# TelematicsBoard.net
KiCad netlist of a schematic drawn in EAGLE
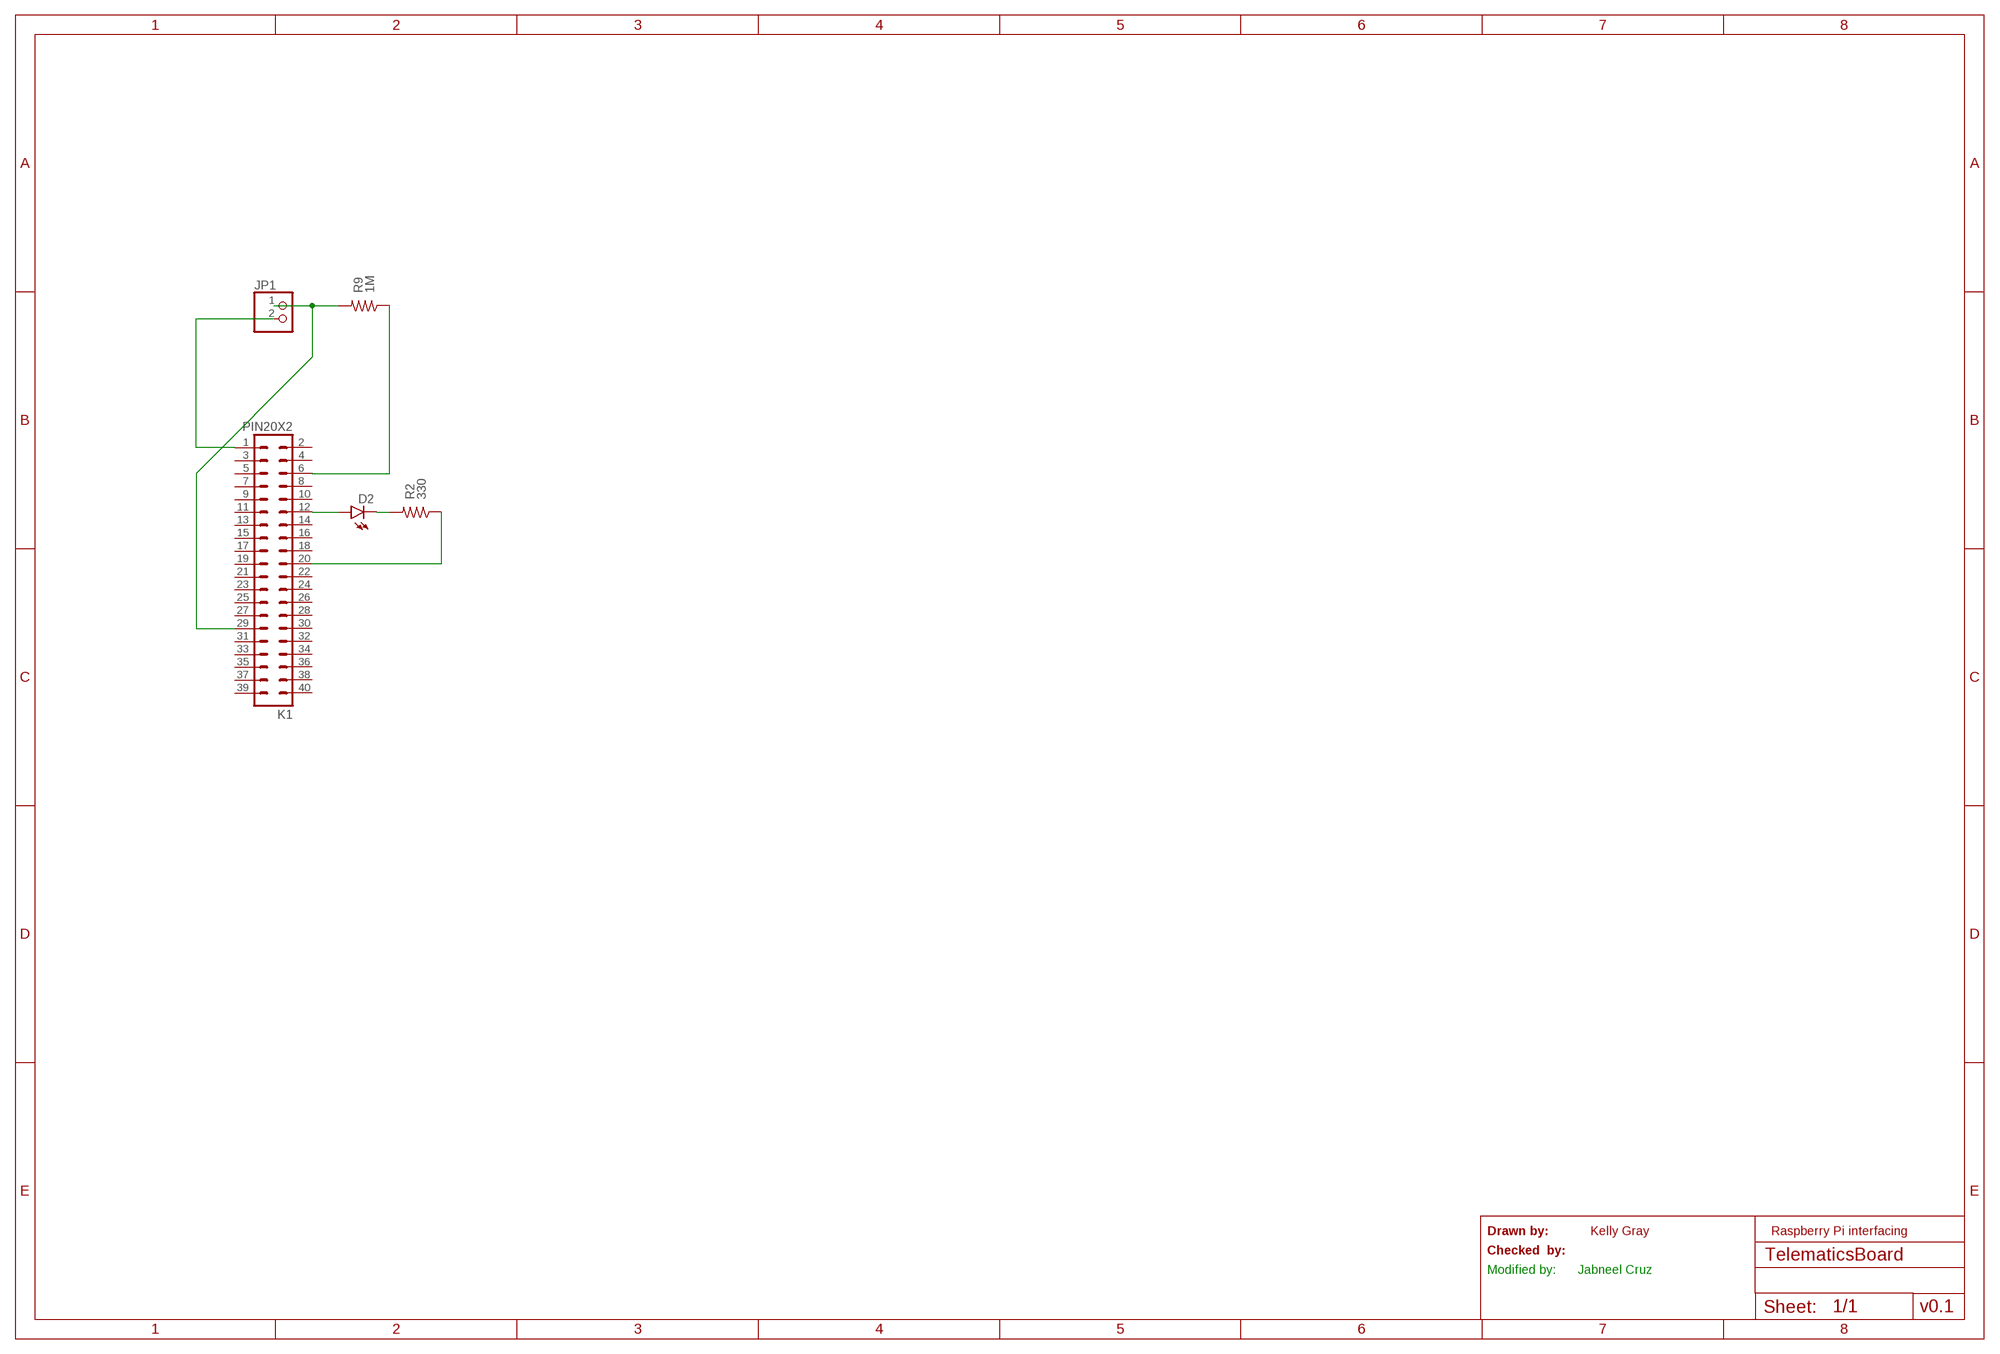
[diagram p0: schematic, sheet 1]

(export (version "E")
  (design (tool "Eeschema 10.0.6"))
  (components
    (comp (ref "D2")
      (value "LED-3MM-NO_SILK")
      (footprint "eagle-import:LED3MM-NS")
      (libsource (lib "eagle-import") (part "LED-3MM-NO_SILK"))
    )
    (comp (ref "JP1")
      (value "PINHD-1X2")
      (footprint "eagle-import:1X02")
      (libsource (lib "eagle-import") (part "PINHD-1X2"))
    )
    (comp (ref "K1")
      (value "PIN20X2")
      (footprint "eagle-import:PIN_20X2")
      (libsource (lib "eagle-import") (part "PIN20X2"))
    )
    (comp (ref "R2")
      (value "330")
      (footprint "eagle-import:AXIAL-0.3")
      (fields (field (name "TOLERANCE") "5%"))
      (libsource (lib "eagle-import") (part "1KOHM-1/4W-1%(PTH)"))
    )
    (comp (ref "R9")
      (value "1M")
      (footprint "eagle-import:AXIAL-0.3")
      (fields (field (name "TOLERANCE") "5%"))
      (libsource (lib "eagle-import") (part "1KOHM-1/4W-1%(PTH)"))
    )
  )
  (nets
    (net (code "1") (name "Net-(D2-C)") (class "Default")
      (node (ref "D2") (pin "K") (pinfunction "C_K") (pintype "passive"))
      (node (ref "R2") (pin "P$2") (pinfunction "2_P$2") (pintype "passive"))
    )
    (net (code "2") (name "Net-(D2-PadA)") (class "Default")
      (node (ref "D2") (pin "A") (pinfunction "A_A") (pintype "passive"))
      (node (ref "K1") (pin "12") (pinfunction "12_12") (pintype "passive"))
    )
    (net (code "3") (name "Net-(JP1-Pad2)") (class "Default")
      (node (ref "JP1") (pin "2") (pinfunction "2_2") (pintype "passive"))
      (node (ref "K1") (pin "1") (pinfunction "1_1") (pintype "passive"))
    )
    (net (code "4") (name "Net-(R2-1)") (class "Default")
      (node (ref "K1") (pin "20") (pinfunction "20_20") (pintype "passive"))
      (node (ref "R2") (pin "P$1") (pinfunction "1_P$1") (pintype "passive"))
    )
    (net (code "5") (name "Net-(R9-1)") (class "Default")
      (node (ref "K1") (pin "6") (pinfunction "6_6") (pintype "passive"))
      (node (ref "R9") (pin "P$1") (pinfunction "1_P$1") (pintype "passive"))
    )
    (net (code "6") (name "Net-(R9-2)") (class "Default")
      (node (ref "JP1") (pin "1") (pinfunction "1_1") (pintype "passive"))
      (node (ref "K1") (pin "29") (pinfunction "29_29") (pintype "passive"))
      (node (ref "R9") (pin "P$2") (pinfunction "2_P$2") (pintype "passive"))
    )
    (net (code "7") (name "unconnected-(K1-Pad2)") (class "Default")
      (node (ref "K1") (pin "2") (pinfunction "2_2") (pintype "passive"))
    )
    (net (code "8") (name "unconnected-(K1-Pad3)") (class "Default")
      (node (ref "K1") (pin "3") (pinfunction "3_3") (pintype "passive"))
    )
    (net (code "9") (name "unconnected-(K1-Pad4)") (class "Default")
      (node (ref "K1") (pin "4") (pinfunction "4_4") (pintype "passive"))
    )
    (net (code "10") (name "unconnected-(K1-Pad5)") (class "Default")
      (node (ref "K1") (pin "5") (pinfunction "5_5") (pintype "passive"))
    )
    (net (code "11") (name "unconnected-(K1-Pad7)") (class "Default")
      (node (ref "K1") (pin "7") (pinfunction "7_7") (pintype "passive"))
    )
    (net (code "12") (name "unconnected-(K1-Pad8)") (class "Default")
      (node (ref "K1") (pin "8") (pinfunction "8_8") (pintype "passive"))
    )
    (net (code "13") (name "unconnected-(K1-Pad9)") (class "Default")
      (node (ref "K1") (pin "9") (pinfunction "9_9") (pintype "passive"))
    )
    (net (code "14") (name "unconnected-(K1-Pad10)") (class "Default")
      (node (ref "K1") (pin "10") (pinfunction "10_10") (pintype "passive"))
    )
    (net (code "15") (name "unconnected-(K1-Pad11)") (class "Default")
      (node (ref "K1") (pin "11") (pinfunction "11_11") (pintype "passive"))
    )
    (net (code "16") (name "unconnected-(K1-Pad13)") (class "Default")
      (node (ref "K1") (pin "13") (pinfunction "13_13") (pintype "passive"))
    )
    (net (code "17") (name "unconnected-(K1-Pad14)") (class "Default")
      (node (ref "K1") (pin "14") (pinfunction "14_14") (pintype "passive"))
    )
    (net (code "18") (name "unconnected-(K1-Pad15)") (class "Default")
      (node (ref "K1") (pin "15") (pinfunction "15_15") (pintype "passive"))
    )
    (net (code "19") (name "unconnected-(K1-Pad16)") (class "Default")
      (node (ref "K1") (pin "16") (pinfunction "16_16") (pintype "passive"))
    )
    (net (code "20") (name "unconnected-(K1-Pad17)") (class "Default")
      (node (ref "K1") (pin "17") (pinfunction "17_17") (pintype "passive"))
    )
    (net (code "21") (name "unconnected-(K1-Pad18)") (class "Default")
      (node (ref "K1") (pin "18") (pinfunction "18_18") (pintype "passive"))
    )
    (net (code "22") (name "unconnected-(K1-Pad19)") (class "Default")
      (node (ref "K1") (pin "19") (pinfunction "19_19") (pintype "passive"))
    )
    (net (code "23") (name "unconnected-(K1-Pad21)") (class "Default")
      (node (ref "K1") (pin "21") (pinfunction "21_21") (pintype "passive"))
    )
    (net (code "24") (name "unconnected-(K1-Pad22)") (class "Default")
      (node (ref "K1") (pin "22") (pinfunction "22_22") (pintype "passive"))
    )
    (net (code "25") (name "unconnected-(K1-Pad23)") (class "Default")
      (node (ref "K1") (pin "23") (pinfunction "23_23") (pintype "passive"))
    )
    (net (code "26") (name "unconnected-(K1-Pad24)") (class "Default")
      (node (ref "K1") (pin "24") (pinfunction "24_24") (pintype "passive"))
    )
    (net (code "27") (name "unconnected-(K1-Pad25)") (class "Default")
      (node (ref "K1") (pin "25") (pinfunction "25_25") (pintype "passive"))
    )
    (net (code "28") (name "unconnected-(K1-Pad26)") (class "Default")
      (node (ref "K1") (pin "26") (pinfunction "26_26") (pintype "passive"))
    )
    (net (code "29") (name "unconnected-(K1-Pad27)") (class "Default")
      (node (ref "K1") (pin "27") (pinfunction "27_27") (pintype "passive"))
    )
    (net (code "30") (name "unconnected-(K1-Pad28)") (class "Default")
      (node (ref "K1") (pin "28") (pinfunction "28_28") (pintype "passive"))
    )
    (net (code "31") (name "unconnected-(K1-Pad30)") (class "Default")
      (node (ref "K1") (pin "30") (pinfunction "30_30") (pintype "passive"))
    )
    (net (code "32") (name "unconnected-(K1-Pad31)") (class "Default")
      (node (ref "K1") (pin "31") (pinfunction "31_31") (pintype "passive"))
    )
    (net (code "33") (name "unconnected-(K1-Pad32)") (class "Default")
      (node (ref "K1") (pin "32") (pinfunction "32_32") (pintype "passive"))
    )
    (net (code "34") (name "unconnected-(K1-Pad33)") (class "Default")
      (node (ref "K1") (pin "33") (pinfunction "33_33") (pintype "passive"))
    )
    (net (code "35") (name "unconnected-(K1-Pad34)") (class "Default")
      (node (ref "K1") (pin "34") (pinfunction "34_34") (pintype "passive"))
    )
    (net (code "36") (name "unconnected-(K1-Pad35)") (class "Default")
      (node (ref "K1") (pin "35") (pinfunction "35_35") (pintype "passive"))
    )
    (net (code "37") (name "unconnected-(K1-Pad36)") (class "Default")
      (node (ref "K1") (pin "36") (pinfunction "36_36") (pintype "passive"))
    )
    (net (code "38") (name "unconnected-(K1-Pad37)") (class "Default")
      (node (ref "K1") (pin "37") (pinfunction "37_37") (pintype "passive"))
    )
    (net (code "39") (name "unconnected-(K1-Pad38)") (class "Default")
      (node (ref "K1") (pin "38") (pinfunction "38_38") (pintype "passive"))
    )
    (net (code "40") (name "unconnected-(K1-Pad39)") (class "Default")
      (node (ref "K1") (pin "39") (pinfunction "39_39") (pintype "passive"))
    )
    (net (code "41") (name "unconnected-(K1-Pad40)") (class "Default")
      (node (ref "K1") (pin "40") (pinfunction "40_40") (pintype "passive"))
    )
  )
)
